# Main_BoardV1.net
KiCad netlist of a schematic drawn in EAGLE
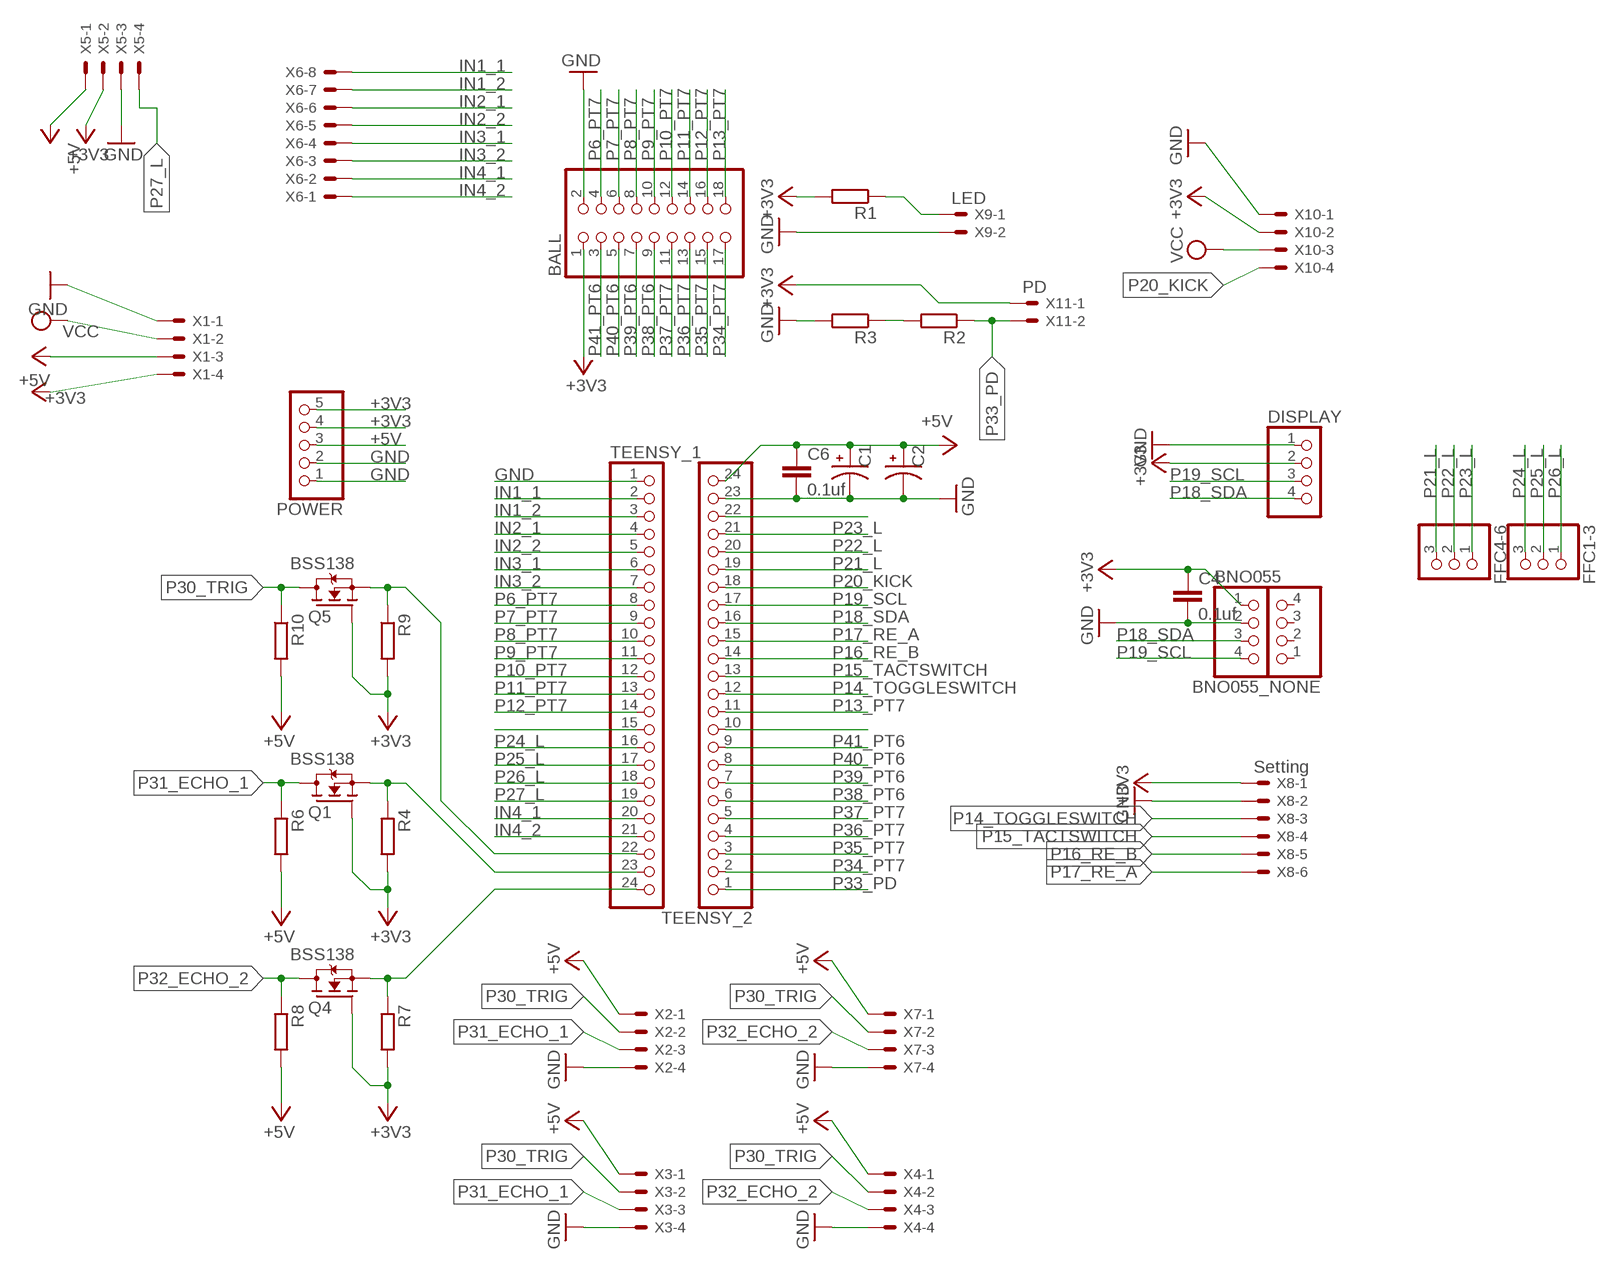
[diagram p0: schematic, sheet 1]

(export (version "E")
  (design (tool "Eeschema 10.0.6"))
  (components
    (comp (ref "BALL")
      (value "PINHD-2X9")
      (footprint "eagle-import:2X09")
      (libsource (lib "eagle-import") (part "PINHD-2X9"))
    )
    (comp (ref "BNO055")
      (value "PINHD-1X4")
      (footprint "eagle-import:1X04")
      (libsource (lib "eagle-import") (part "PINHD-1X4"))
    )
    (comp (ref "BNO055_NONE")
      (value "PINHD-1X4")
      (footprint "eagle-import:1X04")
      (libsource (lib "eagle-import") (part "PINHD-1X4"))
    )
    (comp (ref "C1")
      (value "EEEFK1E332AM")
      (footprint "eagle-import:CAP_EEEFK1E332AM")
      (fields (field (name "MF") "Panasonic"))
      (libsource (lib "eagle-import") (part "EEEFK1E332AM"))
    )
    (comp (ref "C2")
      (value "EEEFK1E332AM")
      (footprint "eagle-import:CAP_EEEFK1E332AM")
      (fields (field (name "MF") "Panasonic"))
      (libsource (lib "eagle-import") (part "EEEFK1E332AM"))
    )
    (comp (ref "C4")
      (value "0.1uf")
      (footprint "eagle-import:C0603")
      (libsource (lib "eagle-import") (part "C-EUC0603"))
    )
    (comp (ref "C6")
      (value "0.1uf")
      (footprint "eagle-import:C0603")
      (libsource (lib "eagle-import") (part "C-EUC0603"))
    )
    (comp (ref "DISPLAY")
      (value "PINHD-1X04_2.54-S")
      (footprint "eagle-import:1X04-S")
      (libsource (lib "eagle-import") (part "PINHD-1X04_2.54-S"))
    )
    (comp (ref "FFC1-3")
      (value "PINHD-1X03_2.54-S")
      (footprint "eagle-import:1X03-S")
      (libsource (lib "eagle-import") (part "PINHD-1X03_2.54-S"))
    )
    (comp (ref "FFC4-6")
      (value "PINHD-1X03_2.54-S")
      (footprint "eagle-import:1X03-S")
      (libsource (lib "eagle-import") (part "PINHD-1X03_2.54-S"))
    )
    (comp (ref "POWER")
      (value "PINHD-1X05_2.54-S")
      (footprint "eagle-import:1X05-S")
      (libsource (lib "eagle-import") (part "PINHD-1X05_2.54-S"))
    )
    (comp (ref "Q1")
      (value "BSS138")
      (footprint "eagle-import:SOT95P240X111-3N")
      (fields (field (name "MF") "ON Semiconductor"))
      (libsource (lib "eagle-import") (part "BSS138"))
    )
    (comp (ref "Q4")
      (value "BSS138")
      (footprint "eagle-import:SOT95P240X111-3N")
      (fields (field (name "MF") "ON Semiconductor"))
      (libsource (lib "eagle-import") (part "BSS138"))
    )
    (comp (ref "Q5")
      (value "BSS138")
      (footprint "eagle-import:SOT95P240X111-3N")
      (fields (field (name "MF") "ON Semiconductor"))
      (libsource (lib "eagle-import") (part "BSS138"))
    )
    (comp (ref "R1")
      (value "R-EU_R0603")
      (footprint "eagle-import:R0603")
      (libsource (lib "eagle-import") (part "R-EU_R0603"))
    )
    (comp (ref "R2")
      (value "R-EU_R0603")
      (footprint "eagle-import:R0603")
      (libsource (lib "eagle-import") (part "R-EU_R0603"))
    )
    (comp (ref "R3")
      (value "R-EU_R0603")
      (footprint "eagle-import:R0603")
      (libsource (lib "eagle-import") (part "R-EU_R0603"))
    )
    (comp (ref "R4")
      (value "R-EU_R0603")
      (footprint "eagle-import:R0603")
      (libsource (lib "eagle-import") (part "R-EU_R0603"))
    )
    (comp (ref "R6")
      (value "R-EU_R0603")
      (footprint "eagle-import:R0603")
      (libsource (lib "eagle-import") (part "R-EU_R0603"))
    )
    (comp (ref "R7")
      (value "R-EU_R0603")
      (footprint "eagle-import:R0603")
      (libsource (lib "eagle-import") (part "R-EU_R0603"))
    )
    (comp (ref "R8")
      (value "R-EU_R0603")
      (footprint "eagle-import:R0603")
      (libsource (lib "eagle-import") (part "R-EU_R0603"))
    )
    (comp (ref "R9")
      (value "R-EU_R0603")
      (footprint "eagle-import:R0603")
      (libsource (lib "eagle-import") (part "R-EU_R0603"))
    )
    (comp (ref "R10")
      (value "R-EU_R0603")
      (footprint "eagle-import:R0603")
      (libsource (lib "eagle-import") (part "R-EU_R0603"))
    )
    (comp (ref "TEENSY_1")
      (value "PINHD-1X24")
      (footprint "eagle-import:1X24")
      (libsource (lib "eagle-import") (part "PINHD-1X24"))
    )
    (comp (ref "TEENSY_2")
      (value "PINHD-1X24")
      (footprint "eagle-import:1X24")
      (libsource (lib "eagle-import") (part "PINHD-1X24"))
    )
    (comp (ref "X1")
      (value "Power")
      (footprint "eagle-import:JST-XH-04-PACKAGE-LONG-PAD")
      (libsource (lib "eagle-import") (part "JST-XH-04-PIN-LONG-PAD"))
    )
    (comp (ref "X2")
      (value "JST-XH-04-PIN-LONG-PAD")
      (footprint "eagle-import:JST-XH-04-PACKAGE-LONG-PAD")
      (libsource (lib "eagle-import") (part "JST-XH-04-PIN-LONG-PAD"))
    )
    (comp (ref "X3")
      (value "JST-XH-04-PIN-LONG-PAD")
      (footprint "eagle-import:JST-XH-04-PACKAGE-LONG-PAD")
      (libsource (lib "eagle-import") (part "JST-XH-04-PIN-LONG-PAD"))
    )
    (comp (ref "X4")
      (value "JST-XH-04-PIN-LONG-PAD")
      (footprint "eagle-import:JST-XH-04-PACKAGE-LONG-PAD")
      (libsource (lib "eagle-import") (part "JST-XH-04-PIN-LONG-PAD"))
    )
    (comp (ref "X5")
      (value "JST-XH-04-PIN-ROUND-PAD")
      (footprint "eagle-import:JST-XH-04-PACKAGE-ROUND-PAD")
      (libsource (lib "eagle-import") (part "Rembrandt Electronics - JST XH Connectors v1-0_JST-XH-04-PIN-ROUND-PAD"))
    )
    (comp (ref "X6")
      (value "Motor")
      (footprint "eagle-import:JST-XH-08-PACKAGE-ROUND-PAD")
      (libsource (lib "eagle-import") (part "JST-XH-08-PIN-ROUND-PAD"))
    )
    (comp (ref "X7")
      (value "JST-XH-04-PIN-LONG-PAD")
      (footprint "eagle-import:JST-XH-04-PACKAGE-LONG-PAD")
      (libsource (lib "eagle-import") (part "JST-XH-04-PIN-LONG-PAD"))
    )
    (comp (ref "X8")
      (value "Setting")
      (footprint "eagle-import:JST-XH-06-PACKAGE-ROUND-PAD")
      (libsource (lib "eagle-import") (part "JST-XH-06-PIN-ROUND-PAD"))
    )
    (comp (ref "X9")
      (value "LED")
      (footprint "eagle-import:JST-XH-02-PACKAGE-ROUND-PAD")
      (libsource (lib "eagle-import") (part "JST-XH-02-PIN-ROUND-PAD"))
    )
    (comp (ref "X10")
      (value "Kicker")
      (footprint "eagle-import:JST-XH-04-PACKAGE-ROUND-PAD")
      (libsource (lib "eagle-import") (part "JST-XH-04-PIN-ROUND-PAD"))
    )
    (comp (ref "X11")
      (value "PD")
      (footprint "eagle-import:JST-XH-02-PACKAGE-ROUND-PAD")
      (libsource (lib "eagle-import") (part "JST-XH-02-PIN-ROUND-PAD"))
    )
  )
  (nets
    (net (code "1") (name "+3V3") (class "Default")
      (node (ref "BALL") (pin "1") (pinfunction "1_1") (pintype "passive"))
      (node (ref "BNO055") (pin "1") (pinfunction "1_1") (pintype "passive"))
      (node (ref "C4") (pin "1") (pinfunction "1_1") (pintype "passive"))
      (node (ref "DISPLAY") (pin "2") (pinfunction "2_2") (pintype "passive"))
      (node (ref "POWER") (pin "4") (pinfunction "4_4") (pintype "passive"))
      (node (ref "POWER") (pin "5") (pinfunction "5_5") (pintype "passive"))
      (node (ref "Q1") (pin "1") (pinfunction "G_1") (pintype "passive"))
      (node (ref "Q4") (pin "1") (pinfunction "G_1") (pintype "passive"))
      (node (ref "Q5") (pin "1") (pinfunction "G_1") (pintype "passive"))
      (node (ref "R1") (pin "2") (pinfunction "2_2") (pintype "passive"))
      (node (ref "R4") (pin "2") (pinfunction "2_2") (pintype "passive"))
      (node (ref "R7") (pin "2") (pinfunction "2_2") (pintype "passive"))
      (node (ref "R9") (pin "2") (pinfunction "2_2") (pintype "passive"))
      (node (ref "X1") (pin "4") (pinfunction "S_4") (pintype "passive"))
      (node (ref "X10") (pin "2") (pinfunction "S_2") (pintype "passive"))
      (node (ref "X11") (pin "1") (pinfunction "S_1") (pintype "passive"))
      (node (ref "X5") (pin "2") (pinfunction "S_2") (pintype "passive"))
      (node (ref "X8") (pin "1") (pinfunction "S_1") (pintype "passive"))
    )
    (net (code "2") (name "+5V") (class "Default")
      (node (ref "C1") (pin "1") (pinfunction "1_1") (pintype "passive"))
      (node (ref "C2") (pin "1") (pinfunction "1_1") (pintype "passive"))
      (node (ref "C6") (pin "1") (pinfunction "1_1") (pintype "passive"))
      (node (ref "POWER") (pin "3") (pinfunction "3_3") (pintype "passive"))
      (node (ref "R10") (pin "2") (pinfunction "2_2") (pintype "passive"))
      (node (ref "R6") (pin "2") (pinfunction "2_2") (pintype "passive"))
      (node (ref "R8") (pin "2") (pinfunction "2_2") (pintype "passive"))
      (node (ref "TEENSY_2") (pin "24") (pinfunction "24_24") (pintype "passive"))
      (node (ref "X1") (pin "3") (pinfunction "S_3") (pintype "passive"))
      (node (ref "X2") (pin "1") (pinfunction "S_1") (pintype "passive"))
      (node (ref "X3") (pin "1") (pinfunction "S_1") (pintype "passive"))
      (node (ref "X4") (pin "1") (pinfunction "S_1") (pintype "passive"))
      (node (ref "X5") (pin "1") (pinfunction "S_1") (pintype "passive"))
      (node (ref "X7") (pin "1") (pinfunction "S_1") (pintype "passive"))
    )
    (net (code "3") (name "/IN1_1") (class "Default")
      (node (ref "TEENSY_1") (pin "2") (pinfunction "2_2") (pintype "passive"))
      (node (ref "X6") (pin "8") (pinfunction "S_8") (pintype "passive"))
    )
    (net (code "4") (name "/IN1_2") (class "Default")
      (node (ref "TEENSY_1") (pin "3") (pinfunction "3_3") (pintype "passive"))
      (node (ref "X6") (pin "7") (pinfunction "S_7") (pintype "passive"))
    )
    (net (code "5") (name "/IN2_1") (class "Default")
      (node (ref "TEENSY_1") (pin "4") (pinfunction "4_4") (pintype "passive"))
      (node (ref "X6") (pin "6") (pinfunction "S_6") (pintype "passive"))
    )
    (net (code "6") (name "/IN2_2") (class "Default")
      (node (ref "TEENSY_1") (pin "5") (pinfunction "5_5") (pintype "passive"))
      (node (ref "X6") (pin "5") (pinfunction "S_5") (pintype "passive"))
    )
    (net (code "7") (name "/IN3_1") (class "Default")
      (node (ref "TEENSY_1") (pin "6") (pinfunction "6_6") (pintype "passive"))
      (node (ref "X6") (pin "4") (pinfunction "S_4") (pintype "passive"))
    )
    (net (code "8") (name "/IN3_2") (class "Default")
      (node (ref "TEENSY_1") (pin "7") (pinfunction "7_7") (pintype "passive"))
      (node (ref "X6") (pin "3") (pinfunction "S_3") (pintype "passive"))
    )
    (net (code "9") (name "/IN4_1") (class "Default")
      (node (ref "TEENSY_1") (pin "20") (pinfunction "20_20") (pintype "passive"))
      (node (ref "X6") (pin "2") (pinfunction "S_2") (pintype "passive"))
    )
    (net (code "10") (name "/IN4_2") (class "Default")
      (node (ref "TEENSY_1") (pin "21") (pinfunction "21_21") (pintype "passive"))
      (node (ref "X6") (pin "1") (pinfunction "S_1") (pintype "passive"))
    )
    (net (code "11") (name "/P6_PT7") (class "Default")
      (node (ref "BALL") (pin "4") (pinfunction "4_4") (pintype "passive"))
      (node (ref "TEENSY_1") (pin "8") (pinfunction "8_8") (pintype "passive"))
    )
    (net (code "12") (name "/P7_PT7") (class "Default")
      (node (ref "BALL") (pin "6") (pinfunction "6_6") (pintype "passive"))
      (node (ref "TEENSY_1") (pin "9") (pinfunction "9_9") (pintype "passive"))
    )
    (net (code "13") (name "/P8_PT7") (class "Default")
      (node (ref "BALL") (pin "8") (pinfunction "8_8") (pintype "passive"))
      (node (ref "TEENSY_1") (pin "10") (pinfunction "10_10") (pintype "passive"))
    )
    (net (code "14") (name "/P9_PT7") (class "Default")
      (node (ref "BALL") (pin "10") (pinfunction "10_10") (pintype "passive"))
      (node (ref "TEENSY_1") (pin "11") (pinfunction "11_11") (pintype "passive"))
    )
    (net (code "15") (name "/P10_PT7") (class "Default")
      (node (ref "BALL") (pin "12") (pinfunction "12_12") (pintype "passive"))
      (node (ref "TEENSY_1") (pin "12") (pinfunction "12_12") (pintype "passive"))
    )
    (net (code "16") (name "/P11_PT7") (class "Default")
      (node (ref "BALL") (pin "14") (pinfunction "14_14") (pintype "passive"))
      (node (ref "TEENSY_1") (pin "13") (pinfunction "13_13") (pintype "passive"))
    )
    (net (code "17") (name "/P12_PT7") (class "Default")
      (node (ref "BALL") (pin "16") (pinfunction "16_16") (pintype "passive"))
      (node (ref "TEENSY_1") (pin "14") (pinfunction "14_14") (pintype "passive"))
    )
    (net (code "18") (name "/P13_PT7") (class "Default")
      (node (ref "BALL") (pin "18") (pinfunction "18_18") (pintype "passive"))
      (node (ref "TEENSY_2") (pin "11") (pinfunction "11_11") (pintype "passive"))
    )
    (net (code "19") (name "/P18_SDA") (class "Default")
      (node (ref "BNO055") (pin "3") (pinfunction "3_3") (pintype "passive"))
      (node (ref "DISPLAY") (pin "4") (pinfunction "4_4") (pintype "passive"))
      (node (ref "TEENSY_2") (pin "16") (pinfunction "16_16") (pintype "passive"))
    )
    (net (code "20") (name "/P19_SCL") (class "Default")
      (node (ref "BNO055") (pin "4") (pinfunction "4_4") (pintype "passive"))
      (node (ref "DISPLAY") (pin "3") (pinfunction "3_3") (pintype "passive"))
      (node (ref "TEENSY_2") (pin "17") (pinfunction "17_17") (pintype "passive"))
    )
    (net (code "21") (name "/P21_L") (class "Default")
      (node (ref "FFC4-6") (pin "3") (pinfunction "3_3") (pintype "passive"))
      (node (ref "TEENSY_2") (pin "19") (pinfunction "19_19") (pintype "passive"))
    )
    (net (code "22") (name "/P22_L") (class "Default")
      (node (ref "FFC4-6") (pin "2") (pinfunction "2_2") (pintype "passive"))
      (node (ref "TEENSY_2") (pin "20") (pinfunction "20_20") (pintype "passive"))
    )
    (net (code "23") (name "/P23_L") (class "Default")
      (node (ref "FFC4-6") (pin "1") (pinfunction "1_1") (pintype "passive"))
      (node (ref "TEENSY_2") (pin "21") (pinfunction "21_21") (pintype "passive"))
    )
    (net (code "24") (name "/P24_L") (class "Default")
      (node (ref "FFC1-3") (pin "3") (pinfunction "3_3") (pintype "passive"))
      (node (ref "TEENSY_1") (pin "16") (pinfunction "16_16") (pintype "passive"))
    )
    (net (code "25") (name "/P25_L") (class "Default")
      (node (ref "FFC1-3") (pin "2") (pinfunction "2_2") (pintype "passive"))
      (node (ref "TEENSY_1") (pin "17") (pinfunction "17_17") (pintype "passive"))
    )
    (net (code "26") (name "/P26_L") (class "Default")
      (node (ref "FFC1-3") (pin "1") (pinfunction "1_1") (pintype "passive"))
      (node (ref "TEENSY_1") (pin "18") (pinfunction "18_18") (pintype "passive"))
    )
    (net (code "27") (name "/P34_PT7") (class "Default")
      (node (ref "BALL") (pin "17") (pinfunction "17_17") (pintype "passive"))
      (node (ref "TEENSY_2") (pin "2") (pinfunction "2_2") (pintype "passive"))
    )
    (net (code "28") (name "/P35_PT7") (class "Default")
      (node (ref "BALL") (pin "15") (pinfunction "15_15") (pintype "passive"))
      (node (ref "TEENSY_2") (pin "3") (pinfunction "3_3") (pintype "passive"))
    )
    (net (code "29") (name "/P36_PT7") (class "Default")
      (node (ref "BALL") (pin "13") (pinfunction "13_13") (pintype "passive"))
      (node (ref "TEENSY_2") (pin "4") (pinfunction "4_4") (pintype "passive"))
    )
    (net (code "30") (name "/P37_PT7") (class "Default")
      (node (ref "BALL") (pin "11") (pinfunction "11_11") (pintype "passive"))
      (node (ref "TEENSY_2") (pin "5") (pinfunction "5_5") (pintype "passive"))
    )
    (net (code "31") (name "/P38_PT6") (class "Default")
      (node (ref "BALL") (pin "9") (pinfunction "9_9") (pintype "passive"))
      (node (ref "TEENSY_2") (pin "6") (pinfunction "6_6") (pintype "passive"))
    )
    (net (code "32") (name "/P39_PT6") (class "Default")
      (node (ref "BALL") (pin "7") (pinfunction "7_7") (pintype "passive"))
      (node (ref "TEENSY_2") (pin "7") (pinfunction "7_7") (pintype "passive"))
    )
    (net (code "33") (name "/P40_PT6") (class "Default")
      (node (ref "BALL") (pin "5") (pinfunction "5_5") (pintype "passive"))
      (node (ref "TEENSY_2") (pin "8") (pinfunction "8_8") (pintype "passive"))
    )
    (net (code "34") (name "/P41_PT6") (class "Default")
      (node (ref "BALL") (pin "3") (pinfunction "3_3") (pintype "passive"))
      (node (ref "TEENSY_2") (pin "9") (pinfunction "9_9") (pintype "passive"))
    )
    (net (code "35") (name "GND") (class "Default")
      (node (ref "BALL") (pin "2") (pinfunction "2_2") (pintype "passive"))
      (node (ref "BNO055") (pin "2") (pinfunction "2_2") (pintype "passive"))
      (node (ref "C1") (pin "2") (pinfunction "2_2") (pintype "passive"))
      (node (ref "C2") (pin "2") (pinfunction "2_2") (pintype "passive"))
      (node (ref "C4") (pin "2") (pinfunction "2_2") (pintype "passive"))
      (node (ref "C6") (pin "2") (pinfunction "2_2") (pintype "passive"))
      (node (ref "DISPLAY") (pin "1") (pinfunction "1_1") (pintype "passive"))
      (node (ref "POWER") (pin "1") (pinfunction "1_1") (pintype "passive"))
      (node (ref "POWER") (pin "2") (pinfunction "2_2") (pintype "passive"))
      (node (ref "R3") (pin "2") (pinfunction "2_2") (pintype "passive"))
      (node (ref "TEENSY_1") (pin "1") (pinfunction "1_1") (pintype "passive"))
      (node (ref "TEENSY_2") (pin "23") (pinfunction "23_23") (pintype "passive"))
      (node (ref "X1") (pin "1") (pinfunction "S_1") (pintype "passive"))
      (node (ref "X10") (pin "1") (pinfunction "S_1") (pintype "passive"))
      (node (ref "X2") (pin "4") (pinfunction "S_4") (pintype "passive"))
      (node (ref "X3") (pin "4") (pinfunction "S_4") (pintype "passive"))
      (node (ref "X4") (pin "4") (pinfunction "S_4") (pintype "passive"))
      (node (ref "X5") (pin "3") (pinfunction "S_3") (pintype "passive"))
      (node (ref "X7") (pin "4") (pinfunction "S_4") (pintype "passive"))
      (node (ref "X8") (pin "2") (pinfunction "S_2") (pintype "passive"))
      (node (ref "X9") (pin "2") (pinfunction "S_2") (pintype "passive"))
    )
    (net (code "36") (name "Net-(Q1-S)") (class "Default")
      (node (ref "Q1") (pin "2") (pinfunction "S_2") (pintype "passive"))
      (node (ref "R4") (pin "1") (pinfunction "1_1") (pintype "passive"))
      (node (ref "TEENSY_1") (pin "23") (pinfunction "23_23") (pintype "passive"))
    )
    (net (code "37") (name "Net-(Q4-S)") (class "Default")
      (node (ref "Q4") (pin "2") (pinfunction "S_2") (pintype "passive"))
      (node (ref "R7") (pin "1") (pinfunction "1_1") (pintype "passive"))
      (node (ref "TEENSY_1") (pin "24") (pinfunction "24_24") (pintype "passive"))
    )
    (net (code "38") (name "Net-(Q5-S)") (class "Default")
      (node (ref "Q5") (pin "2") (pinfunction "S_2") (pintype "passive"))
      (node (ref "R9") (pin "1") (pinfunction "1_1") (pintype "passive"))
      (node (ref "TEENSY_1") (pin "22") (pinfunction "22_22") (pintype "passive"))
    )
    (net (code "39") (name "Net-(R2-Pad2)") (class "Default")
      (node (ref "R2") (pin "2") (pinfunction "2_2") (pintype "passive"))
      (node (ref "R3") (pin "1") (pinfunction "1_1") (pintype "passive"))
    )
    (net (code "40") (name "Net-(X9A-S)") (class "Default")
      (node (ref "R1") (pin "1") (pinfunction "1_1") (pintype "passive"))
      (node (ref "X9") (pin "1") (pinfunction "S_1") (pintype "passive"))
    )
    (net (code "41") (name "P14_TOGGLESWITCH") (class "Default")
      (node (ref "TEENSY_2") (pin "12") (pinfunction "12_12") (pintype "passive"))
      (node (ref "X8") (pin "3") (pinfunction "S_3") (pintype "passive"))
    )
    (net (code "42") (name "P15_TACTSWITCH") (class "Default")
      (node (ref "TEENSY_2") (pin "13") (pinfunction "13_13") (pintype "passive"))
      (node (ref "X8") (pin "4") (pinfunction "S_4") (pintype "passive"))
    )
    (net (code "43") (name "P16_RE_B") (class "Default")
      (node (ref "TEENSY_2") (pin "14") (pinfunction "14_14") (pintype "passive"))
      (node (ref "X8") (pin "5") (pinfunction "S_5") (pintype "passive"))
    )
    (net (code "44") (name "P17_RE_A") (class "Default")
      (node (ref "TEENSY_2") (pin "15") (pinfunction "15_15") (pintype "passive"))
      (node (ref "X8") (pin "6") (pinfunction "S_6") (pintype "passive"))
    )
    (net (code "45") (name "P20_KICK") (class "Default")
      (node (ref "TEENSY_2") (pin "18") (pinfunction "18_18") (pintype "passive"))
      (node (ref "X10") (pin "4") (pinfunction "S_4") (pintype "passive"))
    )
    (net (code "46") (name "P27_L") (class "Default")
      (node (ref "TEENSY_1") (pin "19") (pinfunction "19_19") (pintype "passive"))
      (node (ref "X5") (pin "4") (pinfunction "S_4") (pintype "passive"))
    )
    (net (code "47") (name "P30_TRIG") (class "Default")
      (node (ref "Q5") (pin "3") (pinfunction "D_3") (pintype "passive"))
      (node (ref "R10") (pin "1") (pinfunction "1_1") (pintype "passive"))
      (node (ref "X2") (pin "2") (pinfunction "S_2") (pintype "passive"))
      (node (ref "X3") (pin "2") (pinfunction "S_2") (pintype "passive"))
      (node (ref "X4") (pin "2") (pinfunction "S_2") (pintype "passive"))
      (node (ref "X7") (pin "2") (pinfunction "S_2") (pintype "passive"))
    )
    (net (code "48") (name "P31_ECHO_1") (class "Default")
      (node (ref "Q1") (pin "3") (pinfunction "D_3") (pintype "passive"))
      (node (ref "R6") (pin "1") (pinfunction "1_1") (pintype "passive"))
      (node (ref "X2") (pin "3") (pinfunction "S_3") (pintype "passive"))
      (node (ref "X3") (pin "3") (pinfunction "S_3") (pintype "passive"))
    )
    (net (code "49") (name "P32_ECHO_2") (class "Default")
      (node (ref "Q4") (pin "3") (pinfunction "D_3") (pintype "passive"))
      (node (ref "R8") (pin "1") (pinfunction "1_1") (pintype "passive"))
      (node (ref "X4") (pin "3") (pinfunction "S_3") (pintype "passive"))
      (node (ref "X7") (pin "3") (pinfunction "S_3") (pintype "passive"))
    )
    (net (code "50") (name "P33_PD") (class "Default")
      (node (ref "R2") (pin "1") (pinfunction "1_1") (pintype "passive"))
      (node (ref "TEENSY_2") (pin "1") (pinfunction "1_1") (pintype "passive"))
      (node (ref "X11") (pin "2") (pinfunction "S_2") (pintype "passive"))
    )
    (net (code "51") (name "VCC") (class "Default")
      (node (ref "X1") (pin "2") (pinfunction "S_2") (pintype "passive"))
      (node (ref "X10") (pin "3") (pinfunction "S_3") (pintype "passive"))
    )
    (net (code "52") (name "unconnected-(BNO055_NONE-Pad1)") (class "Default")
      (node (ref "BNO055_NONE") (pin "1") (pinfunction "1_1") (pintype "passive"))
    )
    (net (code "53") (name "unconnected-(BNO055_NONE-Pad2)") (class "Default")
      (node (ref "BNO055_NONE") (pin "2") (pinfunction "2_2") (pintype "passive"))
    )
    (net (code "54") (name "unconnected-(BNO055_NONE-Pad3)") (class "Default")
      (node (ref "BNO055_NONE") (pin "3") (pinfunction "3_3") (pintype "passive"))
    )
    (net (code "55") (name "unconnected-(BNO055_NONE-Pad4)") (class "Default")
      (node (ref "BNO055_NONE") (pin "4") (pinfunction "4_4") (pintype "passive"))
    )
    (net (code "56") (name "unconnected-(TEENSY_1-Pad15)") (class "Default")
      (node (ref "TEENSY_1") (pin "15") (pinfunction "15_15") (pintype "passive"))
    )
    (net (code "57") (name "unconnected-(TEENSY_2-Pad10)") (class "Default")
      (node (ref "TEENSY_2") (pin "10") (pinfunction "10_10") (pintype "passive"))
    )
    (net (code "58") (name "unconnected-(TEENSY_2-Pad22)") (class "Default")
      (node (ref "TEENSY_2") (pin "22") (pinfunction "22_22") (pintype "passive"))
    )
  )
)
